# Qwiic_AS3935_Lightning_Detector.net
KiCad netlist of a schematic drawn in EAGLE
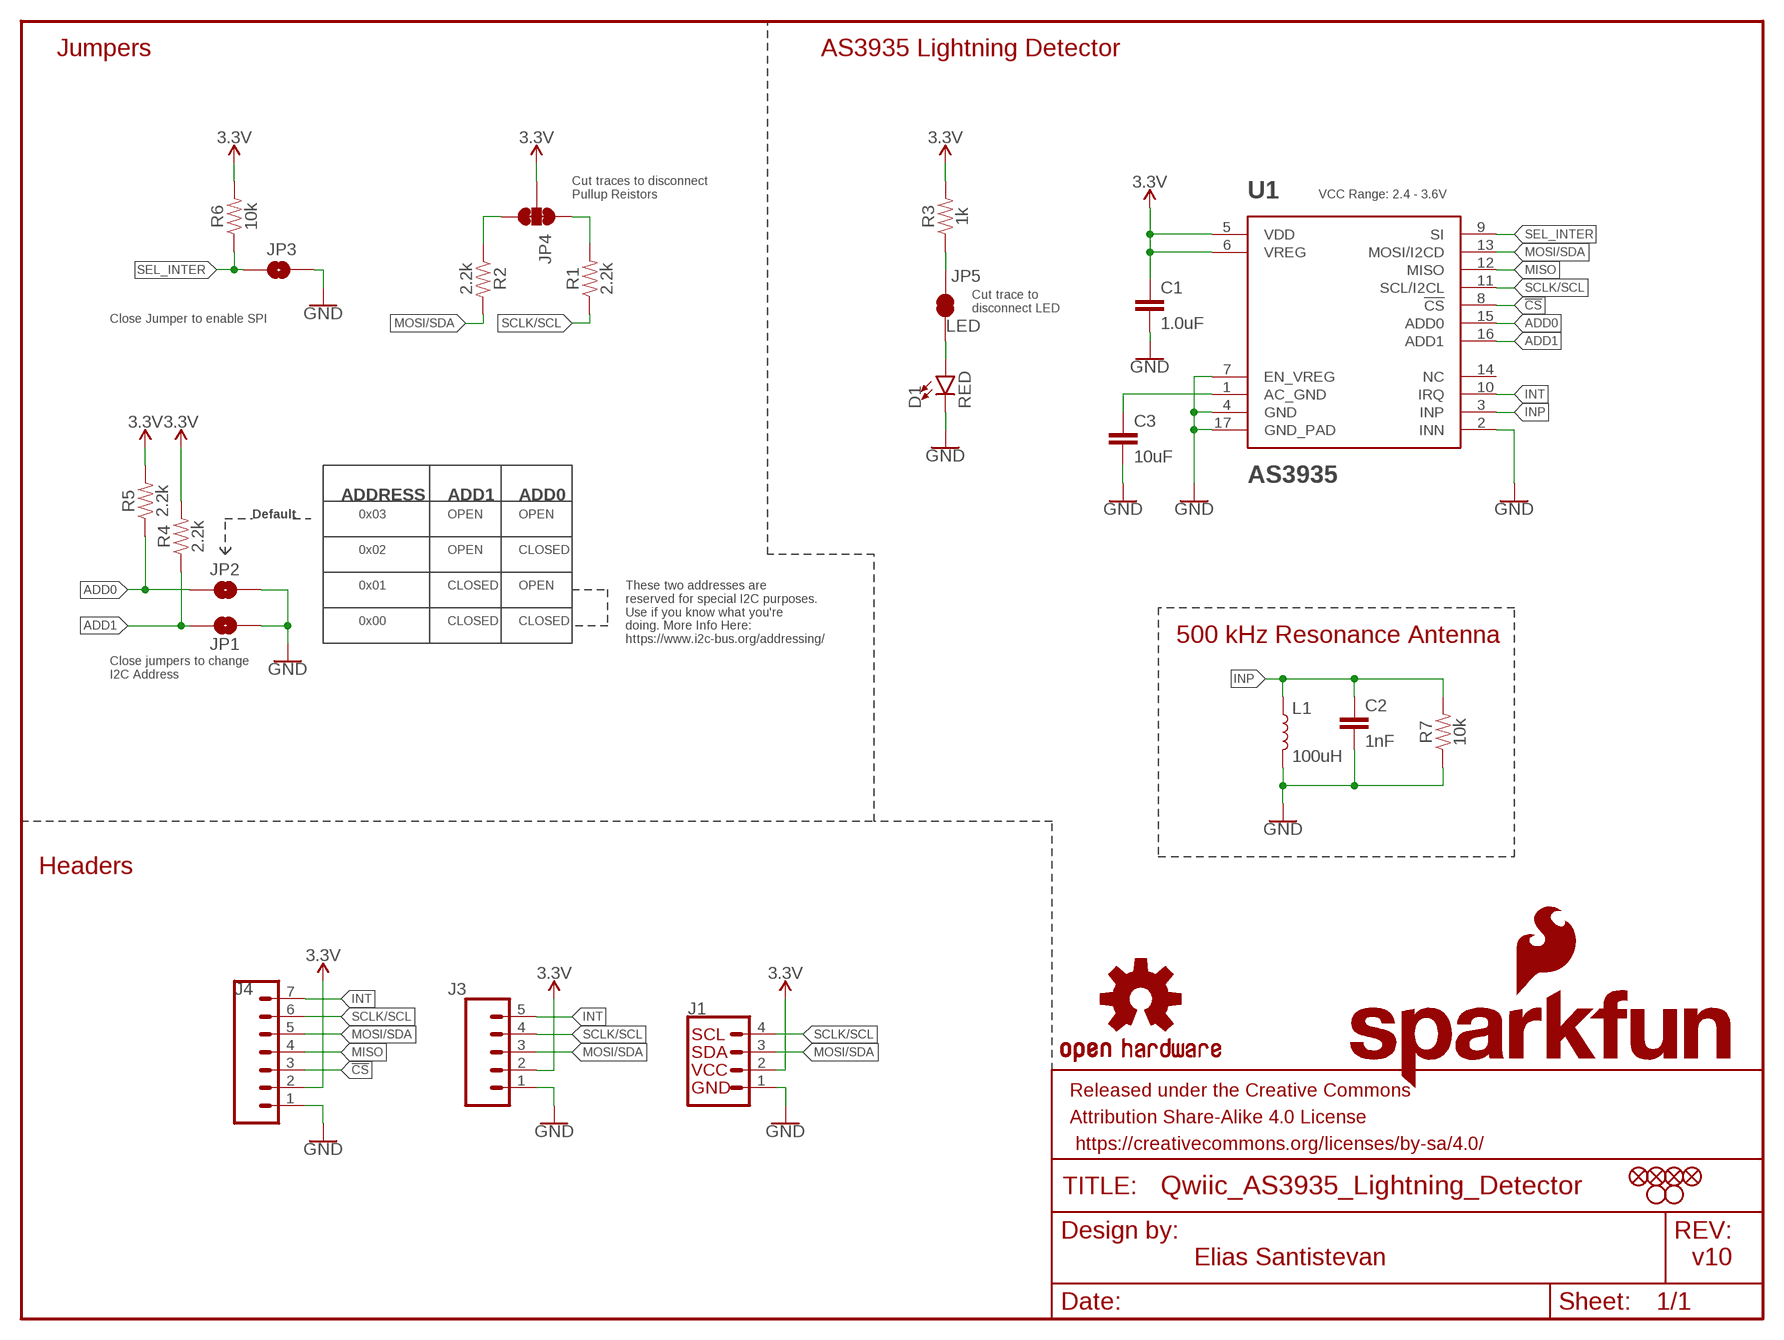
[diagram p0: schematic, sheet 1]

(export (version "E")
  (design (tool "Eeschema 10.0.6"))
  (components
    (comp (ref "C1")
      (value "1.0uF")
      (footprint "eagle-import:0603")
      (libsource (lib "eagle-import") (part "1.0UF-0603-16V-10%"))
    )
    (comp (ref "C2")
      (value "1nF")
      (footprint "eagle-import:0603")
      (libsource (lib "eagle-import") (part "1.0NF/1000PF-0603-50V-10%"))
    )
    (comp (ref "C3")
      (value "10uF")
      (footprint "eagle-import:0603")
      (libsource (lib "eagle-import") (part "10UF-0603-6.3V-20%"))
    )
    (comp (ref "D1")
      (value "RED")
      (footprint "eagle-import:LED-0603")
      (libsource (lib "eagle-import") (part "LED-RED0603"))
    )
    (comp (ref "FD1")
      (value "FIDUCIAL1X2")
      (footprint "eagle-import:FIDUCIAL-1X2")
      (libsource (lib "eagle-import") (part "FIDUCIAL1X2"))
    )
    (comp (ref "FD2")
      (value "FIDUCIAL1X2")
      (footprint "eagle-import:FIDUCIAL-1X2")
      (libsource (lib "eagle-import") (part "FIDUCIAL1X2"))
    )
    (comp (ref "FD3")
      (value "FIDUCIAL1X2")
      (footprint "eagle-import:FIDUCIAL-1X2")
      (libsource (lib "eagle-import") (part "FIDUCIAL1X2"))
    )
    (comp (ref "FD4")
      (value "FIDUCIAL1X2")
      (footprint "eagle-import:FIDUCIAL-1X2")
      (libsource (lib "eagle-import") (part "FIDUCIAL1X2"))
    )
    (comp (ref "FRAME1")
      (value "FRAME-LETTER")
      (footprint "eagle-import:CREATIVE_COMMONS")
      (libsource (lib "eagle-import") (part "FRAME-LETTER"))
    )
    (comp (ref "H1")
      (value "STAND-OFFTIGHT")
      (footprint "eagle-import:STAND-OFF-TIGHT")
      (libsource (lib "eagle-import") (part "STAND-OFFTIGHT"))
    )
    (comp (ref "H2")
      (value "STAND-OFFTIGHT")
      (footprint "eagle-import:STAND-OFF-TIGHT")
      (libsource (lib "eagle-import") (part "STAND-OFFTIGHT"))
    )
    (comp (ref "J1")
      (value "QWIIC_CONNECTORJS-1MM")
      (footprint "eagle-import:JST04_1MM_RA")
      (libsource (lib "eagle-import") (part "QWIIC_CONNECTORJS-1MM"))
    )
    (comp (ref "J3")
      (value "CONN_05NO_SILK")
      (footprint "eagle-import:1X05_NO_SILK")
      (libsource (lib "eagle-import") (part "CONN_05NO_SILK"))
    )
    (comp (ref "J4")
      (value "CONN_07NO_SILK")
      (footprint "eagle-import:1X07_NO_SILK")
      (libsource (lib "eagle-import") (part "CONN_07NO_SILK"))
    )
    (comp (ref "JP1")
      (value "JUMPER-SMT_2_NO_SILK")
      (footprint "eagle-import:SMT-JUMPER_2_NO_SILK")
      (libsource (lib "eagle-import") (part "JUMPER-SMT_2_NO_SILK"))
    )
    (comp (ref "JP2")
      (value "JUMPER-SMT_2_NO_SILK")
      (footprint "eagle-import:SMT-JUMPER_2_NO_SILK")
      (libsource (lib "eagle-import") (part "JUMPER-SMT_2_NO_SILK"))
    )
    (comp (ref "JP3")
      (value "JUMPER-SMT_2_NO_SILK")
      (footprint "eagle-import:SMT-JUMPER_2_NO_SILK")
      (libsource (lib "eagle-import") (part "JUMPER-SMT_2_NO_SILK"))
    )
    (comp (ref "JP4")
      (value "JUMPER-SMT_3_2-NC_TRACE_SILK")
      (footprint "eagle-import:SMT-JUMPER_3_2-NC_TRACE_SILK")
      (libsource (lib "eagle-import") (part "JUMPER-SMT_3_2-NC_TRACE_SILK"))
    )
    (comp (ref "JP5")
      (value "LED")
      (footprint "eagle-import:SMT-JUMPER_2_NC_TRACE_SILK")
      (libsource (lib "eagle-import") (part "JUMPER-SMT_2_NC_TRACE_SILK"))
    )
    (comp (ref "L1")
      (value "100uH")
      (footprint "eagle-import:MA5532-AE")
      (libsource (lib "eagle-import") (part "MA5532-AE"))
    )
    (comp (ref "LOGO1")
      (value "OSHW-LOGOS")
      (footprint "eagle-import:OSHW-LOGO-S")
      (libsource (lib "eagle-import") (part "OSHW-LOGOS"))
    )
    (comp (ref "LOGO2")
      (value "SFE_LOGO_NAME.1_INCH")
      (footprint "eagle-import:SFE_LOGO_NAME_.1")
      (libsource (lib "eagle-import") (part "SFE_LOGO_NAME.1_INCH"))
    )
    (comp (ref "LOGO3")
      (value "SFE_LOGO_FLAME.1_INCH")
      (footprint "eagle-import:SFE_LOGO_FLAME_.1")
      (libsource (lib "eagle-import") (part "SFE_LOGO_FLAME.1_INCH"))
    )
    (comp (ref "R1")
      (value "2.2k")
      (footprint "eagle-import:0603")
      (libsource (lib "eagle-import") (part "2.2KOHM-0603-1/10W-1%"))
    )
    (comp (ref "R2")
      (value "2.2k")
      (footprint "eagle-import:0603")
      (libsource (lib "eagle-import") (part "2.2KOHM-0603-1/10W-1%"))
    )
    (comp (ref "R3")
      (value "1k")
      (footprint "eagle-import:0603")
      (libsource (lib "eagle-import") (part "1KOHM-0603-1/10W-1%"))
    )
    (comp (ref "R4")
      (value "2.2k")
      (footprint "eagle-import:0603")
      (libsource (lib "eagle-import") (part "2.2KOHM-0603-1/10W-1%"))
    )
    (comp (ref "R5")
      (value "2.2k")
      (footprint "eagle-import:0603")
      (libsource (lib "eagle-import") (part "2.2KOHM-0603-1/10W-1%"))
    )
    (comp (ref "R6")
      (value "10k")
      (footprint "eagle-import:0603")
      (libsource (lib "eagle-import") (part "10KOHM-0603-1/10W-1%"))
    )
    (comp (ref "R7")
      (value "10k")
      (footprint "eagle-import:0603")
      (libsource (lib "eagle-import") (part "10KOHM-0603-1/10W-1%"))
    )
    (comp (ref "U1")
      (value "AS3935")
      (footprint "eagle-import:16LD_MLPQ")
      (libsource (lib "eagle-import") (part "AS3935QFN"))
    )
  )
  (nets
    (net (code "1") (name "/~{CS}") (class "Default")
      (node (ref "J4") (pin "3") (pinfunction "3_3") (pintype "passive"))
      (node (ref "U1") (pin "8") (pinfunction "~{CS}_8") (pintype "input"))
    )
    (net (code "2") (name "3.3V") (class "Default")
      (node (ref "C1") (pin "1") (pinfunction "1_1") (pintype "passive"))
      (node (ref "J1") (pin "2") (pinfunction "2_2") (pintype "power_in"))
      (node (ref "J3") (pin "2") (pinfunction "2_2") (pintype "passive"))
      (node (ref "J4") (pin "2") (pinfunction "2_2") (pintype "passive"))
      (node (ref "JP4") (pin "2") (pinfunction "2_2") (pintype "passive"))
      (node (ref "R3") (pin "2") (pinfunction "2_2") (pintype "passive"))
      (node (ref "R4") (pin "2") (pinfunction "2_2") (pintype "passive"))
      (node (ref "R5") (pin "2") (pinfunction "2_2") (pintype "passive"))
      (node (ref "R6") (pin "2") (pinfunction "2_2") (pintype "passive"))
      (node (ref "U1") (pin "5") (pinfunction "VDD_5") (pintype "power_in"))
      (node (ref "U1") (pin "6") (pinfunction "VREG_6") (pintype "power_in"))
    )
    (net (code "3") (name "ADD0") (class "Default")
      (node (ref "JP2") (pin "1") (pinfunction "1_1") (pintype "passive"))
      (node (ref "R5") (pin "1") (pinfunction "1_1") (pintype "passive"))
      (node (ref "U1") (pin "15") (pinfunction "ADD0_15") (pintype "input"))
    )
    (net (code "4") (name "ADD1") (class "Default")
      (node (ref "JP1") (pin "1") (pinfunction "1_1") (pintype "passive"))
      (node (ref "R4") (pin "1") (pinfunction "1_1") (pintype "passive"))
      (node (ref "U1") (pin "16") (pinfunction "ADD1_16") (pintype "input"))
    )
    (net (code "5") (name "GND") (class "Default")
      (node (ref "C1") (pin "2") (pinfunction "2_2") (pintype "passive"))
      (node (ref "C2") (pin "2") (pinfunction "2_2") (pintype "passive"))
      (node (ref "C3") (pin "2") (pinfunction "2_2") (pintype "passive"))
      (node (ref "D1") (pin "C") (pinfunction "C_C") (pintype "passive"))
      (node (ref "J1") (pin "1") (pinfunction "1_1") (pintype "power_in"))
      (node (ref "J3") (pin "1") (pinfunction "1_1") (pintype "passive"))
      (node (ref "J4") (pin "1") (pinfunction "1_1") (pintype "passive"))
      (node (ref "JP1") (pin "2") (pinfunction "2_2") (pintype "passive"))
      (node (ref "JP2") (pin "2") (pinfunction "2_2") (pintype "passive"))
      (node (ref "JP3") (pin "2") (pinfunction "2_2") (pintype "passive"))
      (node (ref "L1") (pin "2") (pinfunction "2_2") (pintype "passive"))
      (node (ref "R7") (pin "1") (pinfunction "1_1") (pintype "passive"))
      (node (ref "U1") (pin "17") (pinfunction "GND_PAD_17") (pintype "power_in"))
      (node (ref "U1") (pin "2") (pinfunction "INN_2") (pintype "bidirectional"))
      (node (ref "U1") (pin "4") (pinfunction "GND_4") (pintype "power_in"))
      (node (ref "U1") (pin "7") (pinfunction "EN_VREG_7") (pintype "bidirectional"))
    )
    (net (code "6") (name "INP") (class "Default")
      (node (ref "C2") (pin "1") (pinfunction "1_1") (pintype "passive"))
      (node (ref "L1") (pin "1") (pinfunction "1_1") (pintype "passive"))
      (node (ref "R7") (pin "2") (pinfunction "2_2") (pintype "passive"))
      (node (ref "U1") (pin "3") (pinfunction "INP_3") (pintype "bidirectional"))
    )
    (net (code "7") (name "INT") (class "Default")
      (node (ref "J3") (pin "5") (pinfunction "5_5") (pintype "passive"))
      (node (ref "J4") (pin "7") (pinfunction "7_7") (pintype "passive"))
      (node (ref "U1") (pin "10") (pinfunction "IRQ_10") (pintype "bidirectional"))
    )
    (net (code "8") (name "MISO") (class "Default")
      (node (ref "J4") (pin "4") (pinfunction "4_4") (pintype "passive"))
      (node (ref "U1") (pin "12") (pinfunction "MISO_12") (pintype "output"))
    )
    (net (code "9") (name "MOSI{slash}SDA") (class "Default")
      (node (ref "J1") (pin "3") (pinfunction "3_3") (pintype "passive"))
      (node (ref "J3") (pin "3") (pinfunction "3_3") (pintype "passive"))
      (node (ref "J4") (pin "5") (pinfunction "5_5") (pintype "passive"))
      (node (ref "R2") (pin "2") (pinfunction "2_2") (pintype "passive"))
      (node (ref "U1") (pin "13") (pinfunction "MOSI/I2CD_13") (pintype "input"))
    )
    (net (code "10") (name "Net-(D1-PadA)") (class "Default")
      (node (ref "D1") (pin "A") (pinfunction "A_A") (pintype "passive"))
      (node (ref "JP5") (pin "1") (pinfunction "1_1") (pintype "passive"))
    )
    (net (code "11") (name "Net-(JP4-Pad1)") (class "Default")
      (node (ref "JP4") (pin "1") (pinfunction "1_1") (pintype "passive"))
      (node (ref "R1") (pin "2") (pinfunction "2_2") (pintype "passive"))
    )
    (net (code "12") (name "Net-(JP4-Pad3)") (class "Default")
      (node (ref "JP4") (pin "3") (pinfunction "3_3") (pintype "passive"))
      (node (ref "R2") (pin "1") (pinfunction "1_1") (pintype "passive"))
    )
    (net (code "13") (name "Net-(JP5-Pad2)") (class "Default")
      (node (ref "JP5") (pin "2") (pinfunction "2_2") (pintype "passive"))
      (node (ref "R3") (pin "1") (pinfunction "1_1") (pintype "passive"))
    )
    (net (code "14") (name "Net-(U1-AC_GND)") (class "Default")
      (node (ref "C3") (pin "1") (pinfunction "1_1") (pintype "passive"))
      (node (ref "U1") (pin "1") (pinfunction "AC_GND_1") (pintype "power_in"))
    )
    (net (code "15") (name "SCLK{slash}SCL") (class "Default")
      (node (ref "J1") (pin "4") (pinfunction "4_4") (pintype "passive"))
      (node (ref "J3") (pin "4") (pinfunction "4_4") (pintype "passive"))
      (node (ref "J4") (pin "6") (pinfunction "6_6") (pintype "passive"))
      (node (ref "R1") (pin "1") (pinfunction "1_1") (pintype "passive"))
      (node (ref "U1") (pin "11") (pinfunction "SCL/I2CL_11") (pintype "input"))
    )
    (net (code "16") (name "SEL_INTER") (class "Default")
      (node (ref "JP3") (pin "1") (pinfunction "1_1") (pintype "passive"))
      (node (ref "R6") (pin "1") (pinfunction "1_1") (pintype "passive"))
      (node (ref "U1") (pin "9") (pinfunction "SI_9") (pintype "input"))
    )
    (net (code "17") (name "unconnected-(U1-NC-Pad14)") (class "Default")
      (node (ref "U1") (pin "14") (pinfunction "NC_14") (pintype "no_connect"))
    )
  )
)
